# DummyLoad__ResistorArray.net
KiCad netlist of a schematic drawn in EAGLE
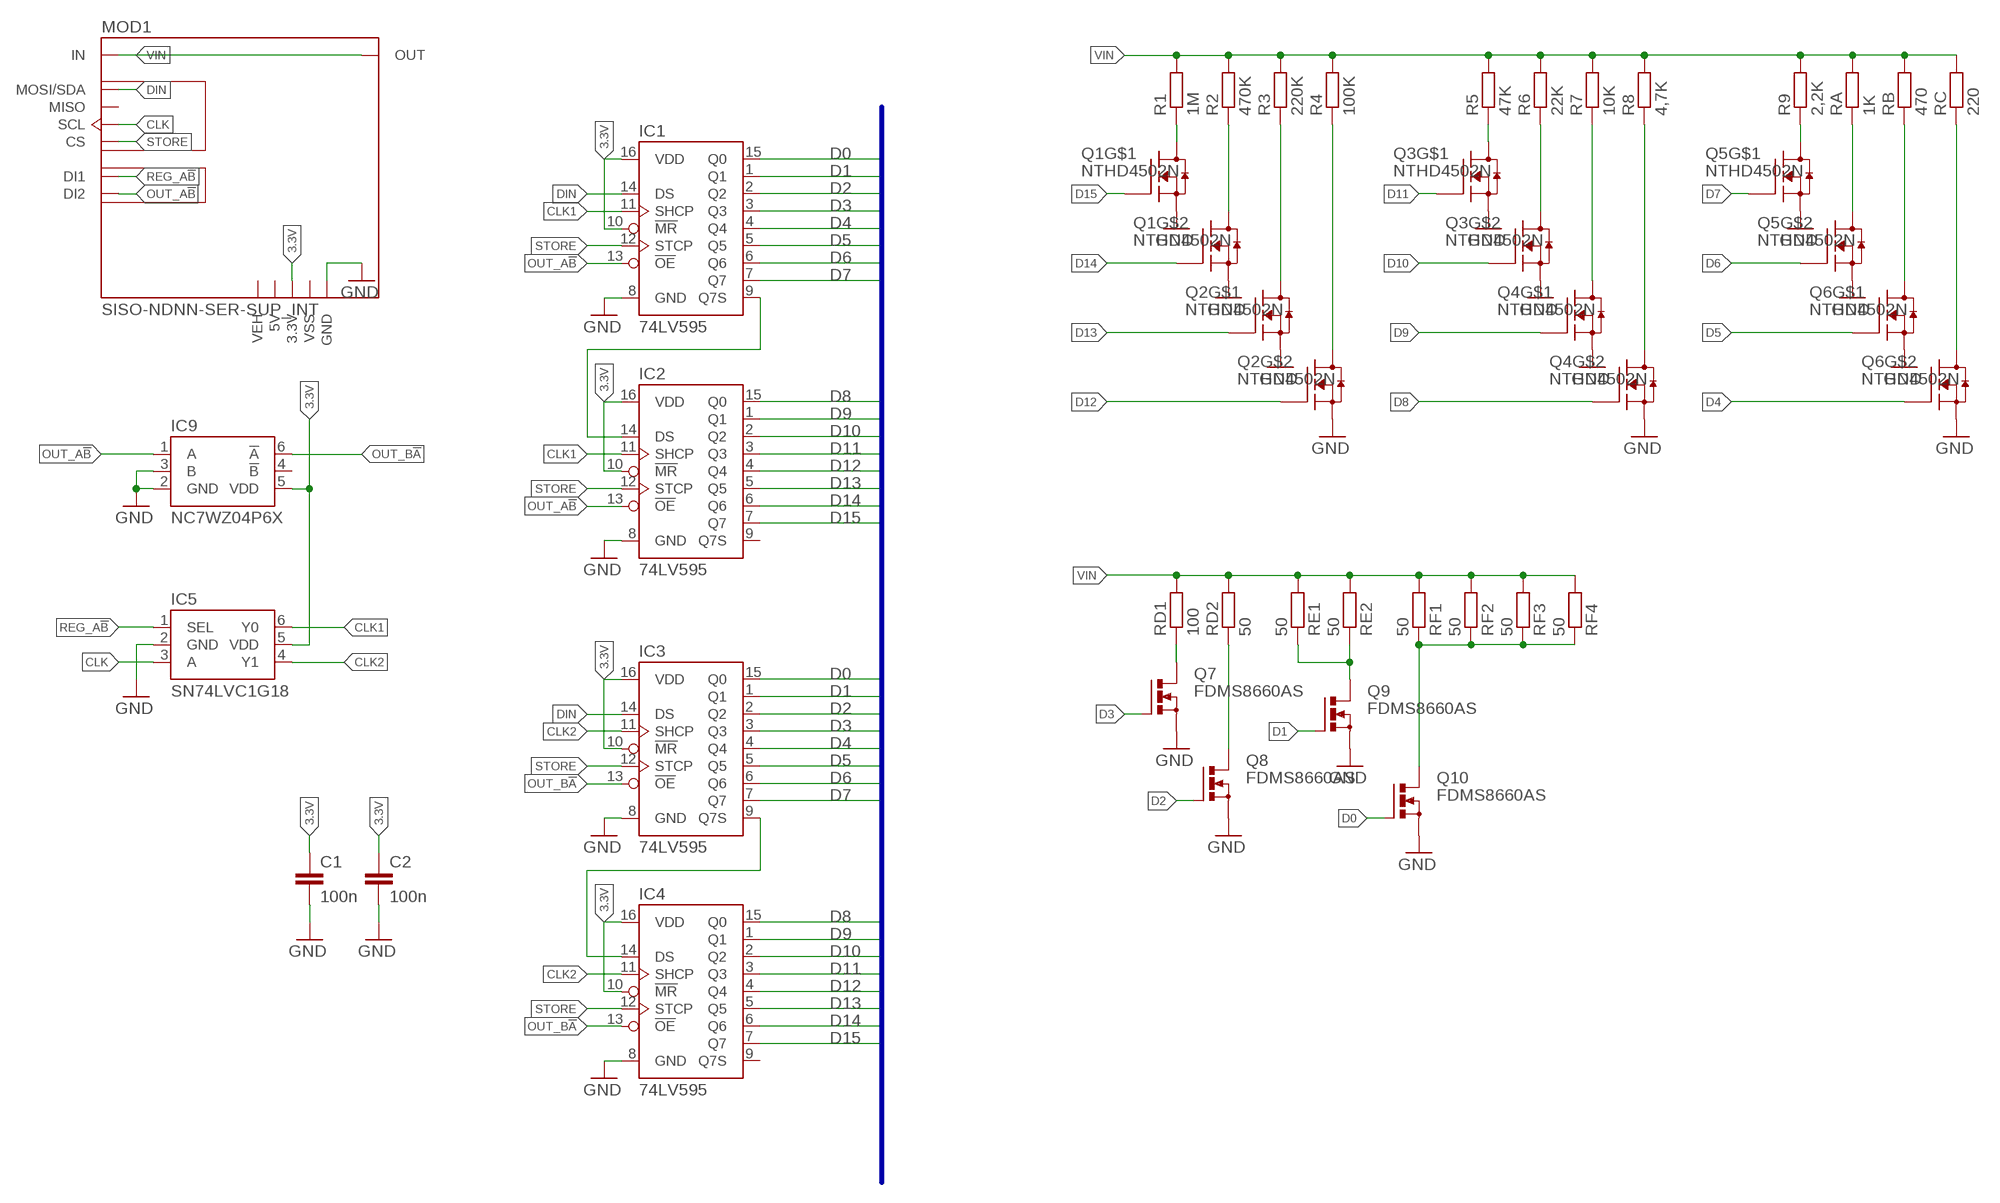
[diagram p0: schematic, sheet 1]

(export (version "E")
  (design (tool "Eeschema 10.0.6"))
  (components
    (comp (ref "C1")
      (value "100n")
      (footprint "eagle-import:C0805K")
      (libsource (lib "eagle-import") (part "C-EUC0805K"))
    )
    (comp (ref "C2")
      (value "100n")
      (footprint "eagle-import:C0805K")
      (libsource (lib "eagle-import") (part "C-EUC0805K"))
    )
    (comp (ref "IC1")
      (value "74LV595")
      (footprint "eagle-import:TSSOP16")
      (libsource (lib "eagle-import") (part "74LV595"))
    )
    (comp (ref "IC2")
      (value "74LV595")
      (footprint "eagle-import:TSSOP16")
      (libsource (lib "eagle-import") (part "74LV595"))
    )
    (comp (ref "IC3")
      (value "74LV595")
      (footprint "eagle-import:TSSOP16")
      (libsource (lib "eagle-import") (part "74LV595"))
    )
    (comp (ref "IC4")
      (value "74LV595")
      (footprint "eagle-import:TSSOP16")
      (libsource (lib "eagle-import") (part "74LV595"))
    )
    (comp (ref "IC5")
      (value "SN74LVC1G18")
      (footprint "eagle-import:SOT65")
      (libsource (lib "eagle-import") (part "SN74LVC1G18"))
    )
    (comp (ref "IC9")
      (value "NC7WZ04P6X")
      (footprint "eagle-import:SOT65P210X110-6N")
      (libsource (lib "eagle-import") (part "NC7WZ04P6X"))
    )
    (comp (ref "MOD1")
      (value "SISO-NDNN-SER-SUP_INT")
      (footprint "eagle-import:SISO-NDNN-SER-SUP")
      (libsource (lib "eagle-import") (part "SISO-NDNN-SER-SUP_INT"))
    )
    (comp (ref "Q1")
      (value "NTHD4502N")
      (footprint "eagle-import:1206A_CHIPFET")
      (libsource (lib "eagle-import") (part "NTHD4502N"))
    )
    (comp (ref "Q2")
      (value "NTHD4502N")
      (footprint "eagle-import:1206A_CHIPFET")
      (libsource (lib "eagle-import") (part "NTHD4502N"))
    )
    (comp (ref "Q3")
      (value "NTHD4502N")
      (footprint "eagle-import:1206A_CHIPFET")
      (libsource (lib "eagle-import") (part "NTHD4502N"))
    )
    (comp (ref "Q4")
      (value "NTHD4502N")
      (footprint "eagle-import:1206A_CHIPFET")
      (libsource (lib "eagle-import") (part "NTHD4502N"))
    )
    (comp (ref "Q5")
      (value "NTHD4502N")
      (footprint "eagle-import:1206A_CHIPFET")
      (libsource (lib "eagle-import") (part "NTHD4502N"))
    )
    (comp (ref "Q6")
      (value "NTHD4502N")
      (footprint "eagle-import:1206A_CHIPFET")
      (libsource (lib "eagle-import") (part "NTHD4502N"))
    )
    (comp (ref "Q7")
      (value "FDMS8660AS")
      (footprint "eagle-import:PG-TDSON-8")
      (libsource (lib "eagle-import") (part "BSZ105N04NS"))
    )
    (comp (ref "Q8")
      (value "FDMS8660AS")
      (footprint "eagle-import:PG-TDSON-8")
      (libsource (lib "eagle-import") (part "BSZ105N04NS"))
    )
    (comp (ref "Q9")
      (value "FDMS8660AS")
      (footprint "eagle-import:PG-TDSON-8")
      (libsource (lib "eagle-import") (part "BSZ105N04NS"))
    )
    (comp (ref "Q10")
      (value "FDMS8660AS")
      (footprint "eagle-import:PG-TDSON-8")
      (libsource (lib "eagle-import") (part "BSZ105N04NS"))
    )
    (comp (ref "R1")
      (value "1M")
      (footprint "eagle-import:R0805")
      (libsource (lib "eagle-import") (part "R-EU_R0805"))
    )
    (comp (ref "R2")
      (value "470K")
      (footprint "eagle-import:R0805")
      (libsource (lib "eagle-import") (part "R-EU_R0805"))
    )
    (comp (ref "R3")
      (value "220K")
      (footprint "eagle-import:R0805")
      (libsource (lib "eagle-import") (part "R-EU_R0805"))
    )
    (comp (ref "R4")
      (value "100K")
      (footprint "eagle-import:R0805")
      (libsource (lib "eagle-import") (part "R-EU_R0805"))
    )
    (comp (ref "R5")
      (value "47K")
      (footprint "eagle-import:R0805")
      (libsource (lib "eagle-import") (part "R-EU_R0805"))
    )
    (comp (ref "R6")
      (value "22K")
      (footprint "eagle-import:R0805")
      (libsource (lib "eagle-import") (part "R-EU_R0805"))
    )
    (comp (ref "R7")
      (value "10K")
      (footprint "eagle-import:R0805")
      (libsource (lib "eagle-import") (part "R-EU_R0805"))
    )
    (comp (ref "R8")
      (value "4,7K")
      (footprint "eagle-import:R0805")
      (libsource (lib "eagle-import") (part "R-EU_R0805"))
    )
    (comp (ref "R9")
      (value "2,2K")
      (footprint "eagle-import:R0805")
      (libsource (lib "eagle-import") (part "R-EU_R0805"))
    )
    (comp (ref "RA")
      (value "1K")
      (footprint "eagle-import:R0805")
      (libsource (lib "eagle-import") (part "R-EU_R0805"))
    )
    (comp (ref "RB")
      (value "470")
      (footprint "eagle-import:R0805")
      (libsource (lib "eagle-import") (part "R-EU_R0805"))
    )
    (comp (ref "RC")
      (value "220")
      (footprint "eagle-import:R0805")
      (libsource (lib "eagle-import") (part "R-EU_R0805"))
    )
    (comp (ref "RD1")
      (value "100")
      (footprint "eagle-import:R1206")
      (libsource (lib "eagle-import") (part "R-EU_R1206"))
    )
    (comp (ref "RD2")
      (value "50")
      (footprint "eagle-import:R1206")
      (libsource (lib "eagle-import") (part "R-EU_R1206"))
    )
    (comp (ref "RE1")
      (value "50")
      (footprint "eagle-import:R1206")
      (libsource (lib "eagle-import") (part "R-EU_R1206"))
    )
    (comp (ref "RE2")
      (value "50")
      (footprint "eagle-import:R1206")
      (libsource (lib "eagle-import") (part "R-EU_R1206"))
    )
    (comp (ref "RF1")
      (value "50")
      (footprint "eagle-import:R1206")
      (libsource (lib "eagle-import") (part "R-EU_R1206"))
    )
    (comp (ref "RF2")
      (value "50")
      (footprint "eagle-import:R1206")
      (libsource (lib "eagle-import") (part "R-EU_R1206"))
    )
    (comp (ref "RF3")
      (value "50")
      (footprint "eagle-import:R1206")
      (libsource (lib "eagle-import") (part "R-EU_R1206"))
    )
    (comp (ref "RF4")
      (value "50")
      (footprint "eagle-import:R1206")
      (libsource (lib "eagle-import") (part "R-EU_R1206"))
    )
  )
  (nets
    (net (code "1") (name "/5V") (class "Default")
      (node (ref "MOD1") (pin "5V") (pinfunction "5V_5V") (pintype "power_in"))
    )
    (net (code "2") (name "/OUT_A~{B}") (class "Default")
      (node (ref "IC1") (pin "13") (pinfunction "~{OE}_13") (pintype "input"))
      (node (ref "IC2") (pin "13") (pinfunction "~{OE}_13") (pintype "input"))
      (node (ref "IC9") (pin "1") (pinfunction "A_1") (pintype "input"))
      (node (ref "MOD1") (pin "DI2") (pinfunction "DI2_DI2") (pintype "output"))
    )
    (net (code "3") (name "/OUT_B~{A}") (class "Default")
      (node (ref "IC3") (pin "13") (pinfunction "~{OE}_13") (pintype "input"))
      (node (ref "IC4") (pin "13") (pinfunction "~{OE}_13") (pintype "input"))
      (node (ref "IC9") (pin "6") (pinfunction "~{A}_6") (pintype "output"))
    )
    (net (code "4") (name "/REG_A~{B}") (class "Default")
      (node (ref "IC5") (pin "1") (pinfunction "SEL_1") (pintype "bidirectional"))
      (node (ref "MOD1") (pin "DI1") (pinfunction "DI1_DI1") (pintype "output"))
    )
    (net (code "5") (name "/VEH") (class "Default")
      (node (ref "MOD1") (pin "VEH") (pinfunction "VEH_VEH") (pintype "power_in"))
    )
    (net (code "6") (name "/VSS") (class "Default")
      (node (ref "MOD1") (pin "VSS") (pinfunction "VSS_VSS") (pintype "power_in"))
    )
    (net (code "7") (name "3.3V") (class "Default")
      (node (ref "C1") (pin "1") (pinfunction "1_1") (pintype "passive"))
      (node (ref "C2") (pin "1") (pinfunction "1_1") (pintype "passive"))
      (node (ref "IC1") (pin "10") (pinfunction "~{MR}_10") (pintype "input"))
      (node (ref "IC1") (pin "16") (pinfunction "VDD_16") (pintype "power_in"))
      (node (ref "IC2") (pin "10") (pinfunction "~{MR}_10") (pintype "input"))
      (node (ref "IC2") (pin "16") (pinfunction "VDD_16") (pintype "power_in"))
      (node (ref "IC3") (pin "10") (pinfunction "~{MR}_10") (pintype "input"))
      (node (ref "IC3") (pin "16") (pinfunction "VDD_16") (pintype "power_in"))
      (node (ref "IC4") (pin "10") (pinfunction "~{MR}_10") (pintype "input"))
      (node (ref "IC4") (pin "16") (pinfunction "VDD_16") (pintype "power_in"))
      (node (ref "IC5") (pin "5") (pinfunction "VDD_5") (pintype "bidirectional"))
      (node (ref "IC9") (pin "5") (pinfunction "VDD_5") (pintype "power_in"))
      (node (ref "MOD1") (pin "3.3V") (pinfunction "3.3V_3.3V") (pintype "power_in"))
    )
    (net (code "8") (name "CLK") (class "Default")
      (node (ref "IC5") (pin "3") (pinfunction "A_3") (pintype "bidirectional"))
      (node (ref "MOD1") (pin "SCL") (pinfunction "SCL_SCL") (pintype "output"))
    )
    (net (code "9") (name "CLK1") (class "Default")
      (node (ref "IC1") (pin "11") (pinfunction "SHCP_11") (pintype "input"))
      (node (ref "IC2") (pin "11") (pinfunction "SHCP_11") (pintype "input"))
      (node (ref "IC5") (pin "6") (pinfunction "Y0_6") (pintype "bidirectional"))
    )
    (net (code "10") (name "CLK2") (class "Default")
      (node (ref "IC3") (pin "11") (pinfunction "SHCP_11") (pintype "input"))
      (node (ref "IC4") (pin "11") (pinfunction "SHCP_11") (pintype "input"))
      (node (ref "IC5") (pin "4") (pinfunction "Y1_4") (pintype "bidirectional"))
    )
    (net (code "11") (name "D0") (class "Default")
      (node (ref "IC1") (pin "15") (pinfunction "Q0_15") (pintype "output"))
      (node (ref "IC3") (pin "15") (pinfunction "Q0_15") (pintype "output"))
      (node (ref "Q10") (pin "4") (pinfunction "G_4") (pintype "passive"))
    )
    (net (code "12") (name "D1") (class "Default")
      (node (ref "IC1") (pin "1") (pinfunction "Q1_1") (pintype "output"))
      (node (ref "IC3") (pin "1") (pinfunction "Q1_1") (pintype "output"))
      (node (ref "Q9") (pin "4") (pinfunction "G_4") (pintype "passive"))
    )
    (net (code "13") (name "D2") (class "Default")
      (node (ref "IC1") (pin "2") (pinfunction "Q2_2") (pintype "output"))
      (node (ref "IC3") (pin "2") (pinfunction "Q2_2") (pintype "output"))
      (node (ref "Q8") (pin "4") (pinfunction "G_4") (pintype "passive"))
    )
    (net (code "14") (name "D3") (class "Default")
      (node (ref "IC1") (pin "3") (pinfunction "Q3_3") (pintype "output"))
      (node (ref "IC3") (pin "3") (pinfunction "Q3_3") (pintype "output"))
      (node (ref "Q7") (pin "4") (pinfunction "G_4") (pintype "passive"))
    )
    (net (code "15") (name "D4") (class "Default")
      (node (ref "IC1") (pin "4") (pinfunction "Q4_4") (pintype "output"))
      (node (ref "IC3") (pin "4") (pinfunction "Q4_4") (pintype "output"))
      (node (ref "Q6") (pin "4") (pinfunction "G_4") (pintype "passive"))
    )
    (net (code "16") (name "D5") (class "Default")
      (node (ref "IC1") (pin "5") (pinfunction "Q5_5") (pintype "output"))
      (node (ref "IC3") (pin "5") (pinfunction "Q5_5") (pintype "output"))
      (node (ref "Q6") (pin "2") (pinfunction "G_2") (pintype "passive"))
    )
    (net (code "17") (name "D6") (class "Default")
      (node (ref "IC1") (pin "6") (pinfunction "Q6_6") (pintype "output"))
      (node (ref "IC3") (pin "6") (pinfunction "Q6_6") (pintype "output"))
      (node (ref "Q5") (pin "4") (pinfunction "G_4") (pintype "passive"))
    )
    (net (code "18") (name "D7") (class "Default")
      (node (ref "IC1") (pin "7") (pinfunction "Q7_7") (pintype "output"))
      (node (ref "IC3") (pin "7") (pinfunction "Q7_7") (pintype "output"))
      (node (ref "Q5") (pin "2") (pinfunction "G_2") (pintype "passive"))
    )
    (net (code "19") (name "D8") (class "Default")
      (node (ref "IC2") (pin "15") (pinfunction "Q0_15") (pintype "output"))
      (node (ref "IC4") (pin "15") (pinfunction "Q0_15") (pintype "output"))
      (node (ref "Q4") (pin "4") (pinfunction "G_4") (pintype "passive"))
    )
    (net (code "20") (name "D9") (class "Default")
      (node (ref "IC2") (pin "1") (pinfunction "Q1_1") (pintype "output"))
      (node (ref "IC4") (pin "1") (pinfunction "Q1_1") (pintype "output"))
      (node (ref "Q4") (pin "2") (pinfunction "G_2") (pintype "passive"))
    )
    (net (code "21") (name "D10") (class "Default")
      (node (ref "IC2") (pin "2") (pinfunction "Q2_2") (pintype "output"))
      (node (ref "IC4") (pin "2") (pinfunction "Q2_2") (pintype "output"))
      (node (ref "Q3") (pin "4") (pinfunction "G_4") (pintype "passive"))
    )
    (net (code "22") (name "D11") (class "Default")
      (node (ref "IC2") (pin "3") (pinfunction "Q3_3") (pintype "output"))
      (node (ref "IC4") (pin "3") (pinfunction "Q3_3") (pintype "output"))
      (node (ref "Q3") (pin "2") (pinfunction "G_2") (pintype "passive"))
    )
    (net (code "23") (name "D12") (class "Default")
      (node (ref "IC2") (pin "4") (pinfunction "Q4_4") (pintype "output"))
      (node (ref "IC4") (pin "4") (pinfunction "Q4_4") (pintype "output"))
      (node (ref "Q2") (pin "4") (pinfunction "G_4") (pintype "passive"))
    )
    (net (code "24") (name "D13") (class "Default")
      (node (ref "IC2") (pin "5") (pinfunction "Q5_5") (pintype "output"))
      (node (ref "IC4") (pin "5") (pinfunction "Q5_5") (pintype "output"))
      (node (ref "Q2") (pin "2") (pinfunction "G_2") (pintype "passive"))
    )
    (net (code "25") (name "D14") (class "Default")
      (node (ref "IC2") (pin "6") (pinfunction "Q6_6") (pintype "output"))
      (node (ref "IC4") (pin "6") (pinfunction "Q6_6") (pintype "output"))
      (node (ref "Q1") (pin "4") (pinfunction "G_4") (pintype "passive"))
    )
    (net (code "26") (name "D15") (class "Default")
      (node (ref "IC2") (pin "7") (pinfunction "Q7_7") (pintype "output"))
      (node (ref "IC4") (pin "7") (pinfunction "Q7_7") (pintype "output"))
      (node (ref "Q1") (pin "2") (pinfunction "G_2") (pintype "passive"))
    )
    (net (code "27") (name "DIN") (class "Default")
      (node (ref "IC1") (pin "14") (pinfunction "DS_14") (pintype "input"))
      (node (ref "IC3") (pin "14") (pinfunction "DS_14") (pintype "input"))
      (node (ref "MOD1") (pin "MOSI/SDA") (pinfunction "MOSI/SDA_MOSI/SDA") (pintype "bidirectional"))
    )
    (net (code "28") (name "GND") (class "Default")
      (node (ref "C1") (pin "2") (pinfunction "2_2") (pintype "passive"))
      (node (ref "C2") (pin "2") (pinfunction "2_2") (pintype "passive"))
      (node (ref "IC1") (pin "8") (pinfunction "GND_8") (pintype "power_in"))
      (node (ref "IC2") (pin "8") (pinfunction "GND_8") (pintype "power_in"))
      (node (ref "IC3") (pin "8") (pinfunction "GND_8") (pintype "power_in"))
      (node (ref "IC4") (pin "8") (pinfunction "GND_8") (pintype "power_in"))
      (node (ref "IC5") (pin "2") (pinfunction "GND_2") (pintype "bidirectional"))
      (node (ref "IC9") (pin "2") (pinfunction "GND_2") (pintype "power_in"))
      (node (ref "IC9") (pin "3") (pinfunction "B_3") (pintype "input"))
      (node (ref "MOD1") (pin "GND1") (pinfunction "GND_GND1") (pintype "power_in"))
      (node (ref "MOD1") (pin "GND2") (pinfunction "GND_GND2") (pintype "power_in"))
      (node (ref "MOD1") (pin "GND3") (pinfunction "GND_GND3") (pintype "power_in"))
      (node (ref "MOD1") (pin "GND4") (pinfunction "GND_GND4") (pintype "power_in"))
      (node (ref "Q1") (pin "1") (pinfunction "S_1") (pintype "passive"))
      (node (ref "Q1") (pin "3") (pinfunction "S_3") (pintype "passive"))
      (node (ref "Q10") (pin "1") (pinfunction "S_1") (pintype "passive"))
      (node (ref "Q10") (pin "2") (pinfunction "S_2") (pintype "passive"))
      (node (ref "Q10") (pin "3") (pinfunction "S_3") (pintype "passive"))
      (node (ref "Q2") (pin "1") (pinfunction "S_1") (pintype "passive"))
      (node (ref "Q2") (pin "3") (pinfunction "S_3") (pintype "passive"))
      (node (ref "Q3") (pin "1") (pinfunction "S_1") (pintype "passive"))
      (node (ref "Q3") (pin "3") (pinfunction "S_3") (pintype "passive"))
      (node (ref "Q4") (pin "1") (pinfunction "S_1") (pintype "passive"))
      (node (ref "Q4") (pin "3") (pinfunction "S_3") (pintype "passive"))
      (node (ref "Q5") (pin "1") (pinfunction "S_1") (pintype "passive"))
      (node (ref "Q5") (pin "3") (pinfunction "S_3") (pintype "passive"))
      (node (ref "Q6") (pin "1") (pinfunction "S_1") (pintype "passive"))
      (node (ref "Q6") (pin "3") (pinfunction "S_3") (pintype "passive"))
      (node (ref "Q7") (pin "1") (pinfunction "S_1") (pintype "passive"))
      (node (ref "Q7") (pin "2") (pinfunction "S_2") (pintype "passive"))
      (node (ref "Q7") (pin "3") (pinfunction "S_3") (pintype "passive"))
      (node (ref "Q8") (pin "1") (pinfunction "S_1") (pintype "passive"))
      (node (ref "Q8") (pin "2") (pinfunction "S_2") (pintype "passive"))
      (node (ref "Q8") (pin "3") (pinfunction "S_3") (pintype "passive"))
      (node (ref "Q9") (pin "1") (pinfunction "S_1") (pintype "passive"))
      (node (ref "Q9") (pin "2") (pinfunction "S_2") (pintype "passive"))
      (node (ref "Q9") (pin "3") (pinfunction "S_3") (pintype "passive"))
    )
    (net (code "29") (name "Net-(IC1-Q7S)") (class "Default")
      (node (ref "IC1") (pin "9") (pinfunction "Q7S_9") (pintype "output"))
      (node (ref "IC2") (pin "14") (pinfunction "DS_14") (pintype "input"))
    )
    (net (code "30") (name "Net-(IC3-Q7S)") (class "Default")
      (node (ref "IC3") (pin "9") (pinfunction "Q7S_9") (pintype "output"))
      (node (ref "IC4") (pin "14") (pinfunction "DS_14") (pintype "input"))
    )
    (net (code "31") (name "Net-(Q1A-D-Pad7)") (class "Default")
      (node (ref "Q1") (pin "7") (pinfunction "D_7") (pintype "passive"))
      (node (ref "Q1") (pin "8") (pinfunction "D_8") (pintype "passive"))
      (node (ref "R1") (pin "1") (pinfunction "1_1") (pintype "passive"))
    )
    (net (code "32") (name "Net-(Q1B-D-Pad5)") (class "Default")
      (node (ref "Q1") (pin "5") (pinfunction "D_5") (pintype "passive"))
      (node (ref "Q1") (pin "6") (pinfunction "D_6") (pintype "passive"))
      (node (ref "R2") (pin "1") (pinfunction "1_1") (pintype "passive"))
    )
    (net (code "33") (name "Net-(Q2A-D-Pad7)") (class "Default")
      (node (ref "Q2") (pin "7") (pinfunction "D_7") (pintype "passive"))
      (node (ref "Q2") (pin "8") (pinfunction "D_8") (pintype "passive"))
      (node (ref "R3") (pin "1") (pinfunction "1_1") (pintype "passive"))
    )
    (net (code "34") (name "Net-(Q2B-D-Pad5)") (class "Default")
      (node (ref "Q2") (pin "5") (pinfunction "D_5") (pintype "passive"))
      (node (ref "Q2") (pin "6") (pinfunction "D_6") (pintype "passive"))
      (node (ref "R4") (pin "1") (pinfunction "1_1") (pintype "passive"))
    )
    (net (code "35") (name "Net-(Q3A-D-Pad7)") (class "Default")
      (node (ref "Q3") (pin "7") (pinfunction "D_7") (pintype "passive"))
      (node (ref "Q3") (pin "8") (pinfunction "D_8") (pintype "passive"))
      (node (ref "R5") (pin "1") (pinfunction "1_1") (pintype "passive"))
    )
    (net (code "36") (name "Net-(Q3B-D-Pad5)") (class "Default")
      (node (ref "Q3") (pin "5") (pinfunction "D_5") (pintype "passive"))
      (node (ref "Q3") (pin "6") (pinfunction "D_6") (pintype "passive"))
      (node (ref "R6") (pin "1") (pinfunction "1_1") (pintype "passive"))
    )
    (net (code "37") (name "Net-(Q4A-D-Pad7)") (class "Default")
      (node (ref "Q4") (pin "7") (pinfunction "D_7") (pintype "passive"))
      (node (ref "Q4") (pin "8") (pinfunction "D_8") (pintype "passive"))
      (node (ref "R7") (pin "1") (pinfunction "1_1") (pintype "passive"))
    )
    (net (code "38") (name "Net-(Q4B-D-Pad5)") (class "Default")
      (node (ref "Q4") (pin "5") (pinfunction "D_5") (pintype "passive"))
      (node (ref "Q4") (pin "6") (pinfunction "D_6") (pintype "passive"))
      (node (ref "R8") (pin "1") (pinfunction "1_1") (pintype "passive"))
    )
    (net (code "39") (name "Net-(Q5A-D-Pad7)") (class "Default")
      (node (ref "Q5") (pin "7") (pinfunction "D_7") (pintype "passive"))
      (node (ref "Q5") (pin "8") (pinfunction "D_8") (pintype "passive"))
      (node (ref "R9") (pin "1") (pinfunction "1_1") (pintype "passive"))
    )
    (net (code "40") (name "Net-(Q5B-D-Pad5)") (class "Default")
      (node (ref "Q5") (pin "5") (pinfunction "D_5") (pintype "passive"))
      (node (ref "Q5") (pin "6") (pinfunction "D_6") (pintype "passive"))
      (node (ref "RA") (pin "1") (pinfunction "1_1") (pintype "passive"))
    )
    (net (code "41") (name "Net-(Q6A-D-Pad7)") (class "Default")
      (node (ref "Q6") (pin "7") (pinfunction "D_7") (pintype "passive"))
      (node (ref "Q6") (pin "8") (pinfunction "D_8") (pintype "passive"))
      (node (ref "RB") (pin "1") (pinfunction "1_1") (pintype "passive"))
    )
    (net (code "42") (name "Net-(Q6B-D-Pad5)") (class "Default")
      (node (ref "Q6") (pin "5") (pinfunction "D_5") (pintype "passive"))
      (node (ref "Q6") (pin "6") (pinfunction "D_6") (pintype "passive"))
      (node (ref "RC") (pin "1") (pinfunction "1_1") (pintype "passive"))
    )
    (net (code "43") (name "Net-(Q7-D-Pad5)") (class "Default")
      (node (ref "Q7") (pin "5") (pinfunction "D_5") (pintype "passive"))
      (node (ref "Q7") (pin "6") (pinfunction "D_6") (pintype "passive"))
      (node (ref "Q7") (pin "7") (pinfunction "D_7") (pintype "passive"))
      (node (ref "Q7") (pin "8") (pinfunction "D_8") (pintype "passive"))
      (node (ref "Q7") (pin "TH") (pinfunction "D_TH") (pintype "passive"))
      (node (ref "RD1") (pin "1") (pinfunction "1_1") (pintype "passive"))
    )
    (net (code "44") (name "Net-(Q8-D-Pad5)") (class "Default")
      (node (ref "Q8") (pin "5") (pinfunction "D_5") (pintype "passive"))
      (node (ref "Q8") (pin "6") (pinfunction "D_6") (pintype "passive"))
      (node (ref "Q8") (pin "7") (pinfunction "D_7") (pintype "passive"))
      (node (ref "Q8") (pin "8") (pinfunction "D_8") (pintype "passive"))
      (node (ref "Q8") (pin "TH") (pinfunction "D_TH") (pintype "passive"))
      (node (ref "RD2") (pin "1") (pinfunction "1_1") (pintype "passive"))
    )
    (net (code "45") (name "Net-(Q9-D-Pad5)") (class "Default")
      (node (ref "Q9") (pin "5") (pinfunction "D_5") (pintype "passive"))
      (node (ref "Q9") (pin "6") (pinfunction "D_6") (pintype "passive"))
      (node (ref "Q9") (pin "7") (pinfunction "D_7") (pintype "passive"))
      (node (ref "Q9") (pin "8") (pinfunction "D_8") (pintype "passive"))
      (node (ref "Q9") (pin "TH") (pinfunction "D_TH") (pintype "passive"))
      (node (ref "RE1") (pin "1") (pinfunction "1_1") (pintype "passive"))
      (node (ref "RE2") (pin "1") (pinfunction "1_1") (pintype "passive"))
    )
    (net (code "46") (name "Net-(Q10-D-Pad5)") (class "Default")
      (node (ref "Q10") (pin "5") (pinfunction "D_5") (pintype "passive"))
      (node (ref "Q10") (pin "6") (pinfunction "D_6") (pintype "passive"))
      (node (ref "Q10") (pin "7") (pinfunction "D_7") (pintype "passive"))
      (node (ref "Q10") (pin "8") (pinfunction "D_8") (pintype "passive"))
      (node (ref "Q10") (pin "TH") (pinfunction "D_TH") (pintype "passive"))
      (node (ref "RF1") (pin "1") (pinfunction "1_1") (pintype "passive"))
      (node (ref "RF2") (pin "1") (pinfunction "1_1") (pintype "passive"))
      (node (ref "RF3") (pin "1") (pinfunction "1_1") (pintype "passive"))
      (node (ref "RF4") (pin "1") (pinfunction "1_1") (pintype "passive"))
    )
    (net (code "47") (name "STORE") (class "Default")
      (node (ref "IC1") (pin "12") (pinfunction "STCP_12") (pintype "input"))
      (node (ref "IC2") (pin "12") (pinfunction "STCP_12") (pintype "input"))
      (node (ref "IC3") (pin "12") (pinfunction "STCP_12") (pintype "input"))
      (node (ref "IC4") (pin "12") (pinfunction "STCP_12") (pintype "input"))
      (node (ref "MOD1") (pin "CS") (pinfunction "CS_CS") (pintype "bidirectional"))
    )
    (net (code "48") (name "VIN") (class "Default")
      (node (ref "MOD1") (pin "IN1") (pinfunction "IN_IN1") (pintype "output"))
      (node (ref "MOD1") (pin "IN2") (pinfunction "IN_IN2") (pintype "output"))
      (node (ref "MOD1") (pin "IN3") (pinfunction "IN_IN3") (pintype "output"))
      (node (ref "MOD1") (pin "IN4") (pinfunction "IN_IN4") (pintype "output"))
      (node (ref "MOD1") (pin "OUT1") (pinfunction "OUT_OUT1") (pintype "input"))
      (node (ref "MOD1") (pin "OUT2") (pinfunction "OUT_OUT2") (pintype "input"))
      (node (ref "MOD1") (pin "OUT3") (pinfunction "OUT_OUT3") (pintype "input"))
      (node (ref "MOD1") (pin "OUT4") (pinfunction "OUT_OUT4") (pintype "input"))
      (node (ref "R1") (pin "2") (pinfunction "2_2") (pintype "passive"))
      (node (ref "R2") (pin "2") (pinfunction "2_2") (pintype "passive"))
      (node (ref "R3") (pin "2") (pinfunction "2_2") (pintype "passive"))
      (node (ref "R4") (pin "2") (pinfunction "2_2") (pintype "passive"))
      (node (ref "R5") (pin "2") (pinfunction "2_2") (pintype "passive"))
      (node (ref "R6") (pin "2") (pinfunction "2_2") (pintype "passive"))
      (node (ref "R7") (pin "2") (pinfunction "2_2") (pintype "passive"))
      (node (ref "R8") (pin "2") (pinfunction "2_2") (pintype "passive"))
      (node (ref "R9") (pin "2") (pinfunction "2_2") (pintype "passive"))
      (node (ref "RA") (pin "2") (pinfunction "2_2") (pintype "passive"))
      (node (ref "RB") (pin "2") (pinfunction "2_2") (pintype "passive"))
      (node (ref "RC") (pin "2") (pinfunction "2_2") (pintype "passive"))
      (node (ref "RD1") (pin "2") (pinfunction "2_2") (pintype "passive"))
      (node (ref "RD2") (pin "2") (pinfunction "2_2") (pintype "passive"))
      (node (ref "RE1") (pin "2") (pinfunction "2_2") (pintype "passive"))
      (node (ref "RE2") (pin "2") (pinfunction "2_2") (pintype "passive"))
      (node (ref "RF1") (pin "2") (pinfunction "2_2") (pintype "passive"))
      (node (ref "RF2") (pin "2") (pinfunction "2_2") (pintype "passive"))
      (node (ref "RF3") (pin "2") (pinfunction "2_2") (pintype "passive"))
      (node (ref "RF4") (pin "2") (pinfunction "2_2") (pintype "passive"))
    )
    (net (code "49") (name "unconnected-(IC2-Q7S-Pad9)") (class "Default")
      (node (ref "IC2") (pin "9") (pinfunction "Q7S_9") (pintype "output"))
    )
    (net (code "50") (name "unconnected-(IC4-Q7S-Pad9)") (class "Default")
      (node (ref "IC4") (pin "9") (pinfunction "Q7S_9") (pintype "output"))
    )
    (net (code "51") (name "unconnected-(IC9-~{B}-Pad4)") (class "Default")
      (node (ref "IC9") (pin "4") (pinfunction "~{B}_4") (pintype "output"))
    )
    (net (code "52") (name "unconnected-(MOD1-PadMISO)") (class "Default")
      (node (ref "MOD1") (pin "MISO") (pinfunction "MISO_MISO") (pintype "bidirectional"))
    )
  )
)
